# RobotBoard4.net
KiCad netlist of a schematic drawn in EAGLE
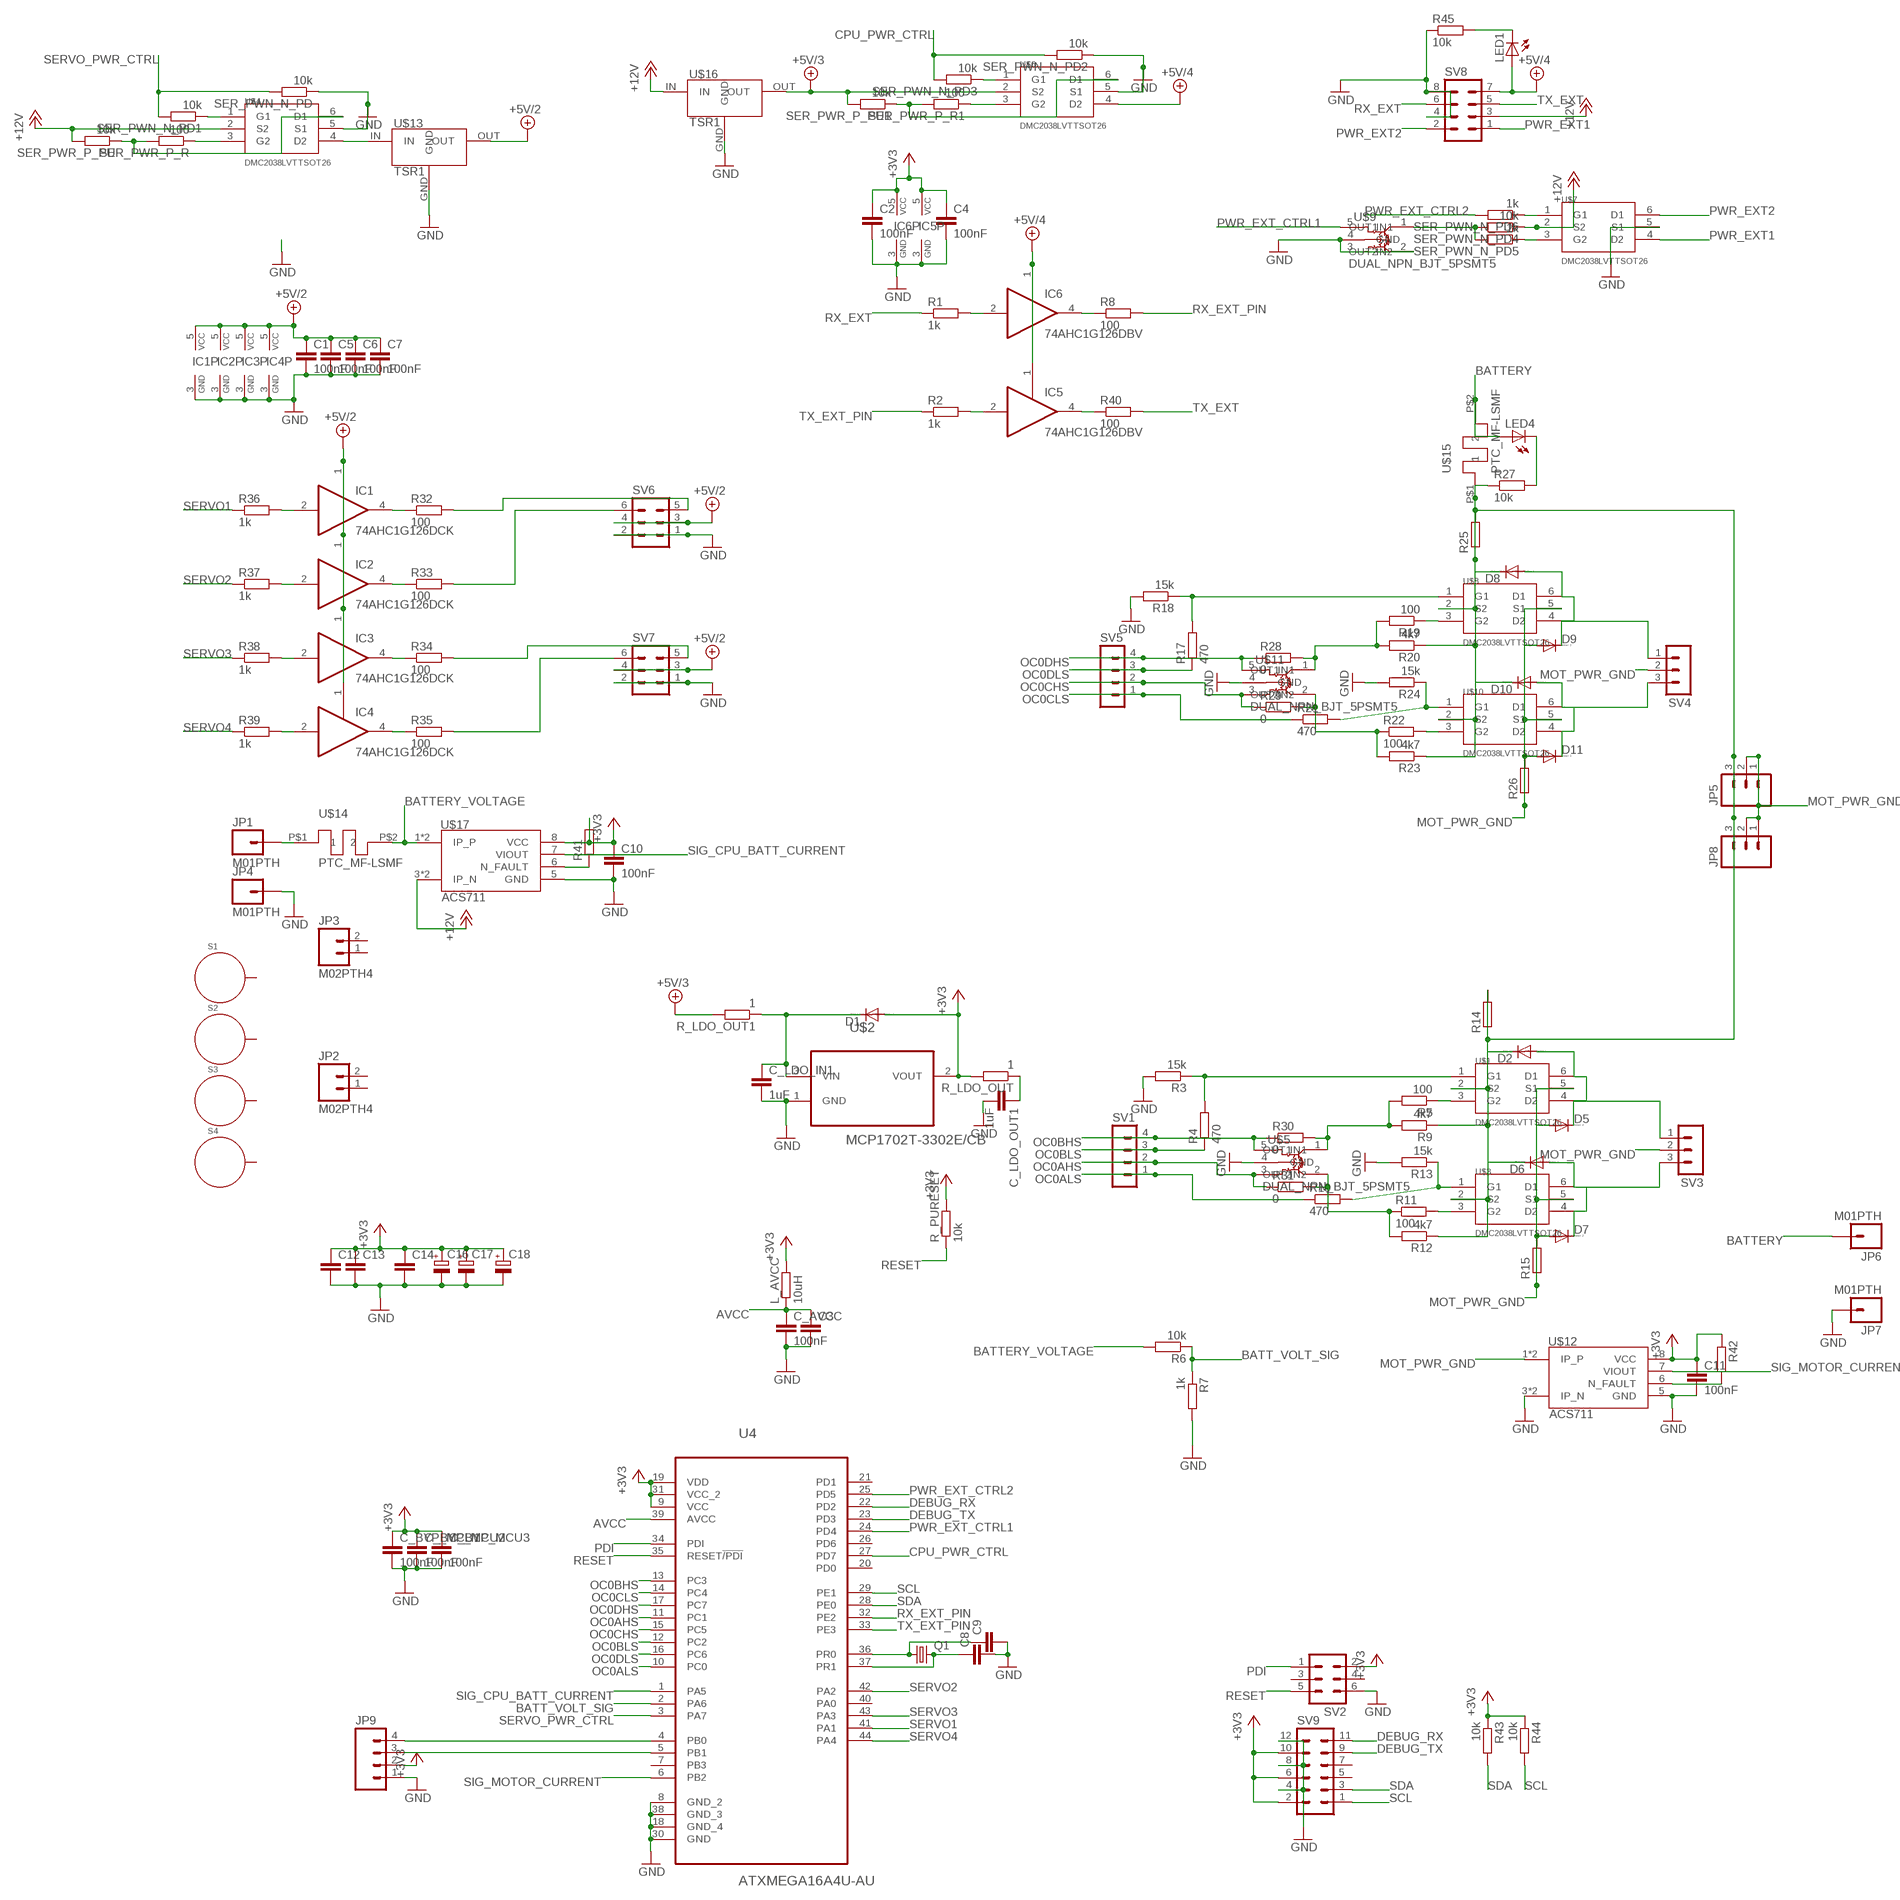
[diagram p0: schematic, sheet 1]

(export (version "E")
  (design (tool "Eeschema 10.0.6"))
  (components
    (comp (ref "C1")
      (value "100nF")
      (footprint "eagle-import:C0603")
      (libsource (lib "eagle-import") (part "C-EUC0603"))
    )
    (comp (ref "C2")
      (value "100nF")
      (footprint "eagle-import:C0603K")
      (libsource (lib "eagle-import") (part "C-EUC0603K"))
    )
    (comp (ref "C3")
      (value "C-EUC1206K")
      (footprint "eagle-import:C1206K")
      (libsource (lib "eagle-import") (part "C-EUC1206K"))
    )
    (comp (ref "C4")
      (value "100nF")
      (footprint "eagle-import:C0603K")
      (libsource (lib "eagle-import") (part "C-EUC0603K"))
    )
    (comp (ref "C5")
      (value "100nF")
      (footprint "eagle-import:C0603")
      (libsource (lib "eagle-import") (part "C-EUC0603"))
    )
    (comp (ref "C6")
      (value "100nF")
      (footprint "eagle-import:C0603")
      (libsource (lib "eagle-import") (part "C-EUC0603"))
    )
    (comp (ref "C7")
      (value "100nF")
      (footprint "eagle-import:C0603")
      (libsource (lib "eagle-import") (part "C-EUC0603"))
    )
    (comp (ref "C8")
      (value "C-EUC0603K")
      (footprint "eagle-import:C0603K")
      (libsource (lib "eagle-import") (part "C-EUC0603K"))
    )
    (comp (ref "C9")
      (value "C-EUC0603K")
      (footprint "eagle-import:C0603K")
      (libsource (lib "eagle-import") (part "C-EUC0603K"))
    )
    (comp (ref "C10")
      (value "100nF")
      (footprint "eagle-import:C0603K")
      (libsource (lib "eagle-import") (part "C-EUC0603K"))
    )
    (comp (ref "C11")
      (value "100nF")
      (footprint "eagle-import:C0603K")
      (libsource (lib "eagle-import") (part "C-EUC0603K"))
    )
    (comp (ref "C12")
      (value "C-EUC0805K")
      (footprint "eagle-import:C0805K")
      (libsource (lib "eagle-import") (part "C-EUC0805K"))
    )
    (comp (ref "C13")
      (value "C-EUC0805K")
      (footprint "eagle-import:C0805K")
      (libsource (lib "eagle-import") (part "C-EUC0805K"))
    )
    (comp (ref "C14")
      (value "C-EUC1210")
      (footprint "eagle-import:C1210")
      (libsource (lib "eagle-import") (part "C-EUC1210"))
    )
    (comp (ref "C16")
      (value "CPOL-EUE2.5-6")
      (footprint "eagle-import:E2,5-6")
      (libsource (lib "eagle-import") (part "CPOL-EUE2.5-6"))
    )
    (comp (ref "C17")
      (value "CPOL-EUE2.5-6")
      (footprint "eagle-import:E2,5-6")
      (libsource (lib "eagle-import") (part "CPOL-EUE2.5-6"))
    )
    (comp (ref "C18")
      (value "CPOL-EU153CLV-0505")
      (footprint "eagle-import:153CLV-0505")
      (libsource (lib "eagle-import") (part "CPOL-EU153CLV-0505"))
    )
    (comp (ref "C_AVCC")
      (value "100nF")
      (footprint "eagle-import:C0603")
      (libsource (lib "eagle-import") (part "C-EUC0603"))
    )
    (comp (ref "C_BYP_MCU1")
      (value "100nF")
      (footprint "eagle-import:C0603")
      (libsource (lib "eagle-import") (part "C-EUC0603"))
    )
    (comp (ref "C_BYP_MCU2")
      (value "100nF")
      (footprint "eagle-import:C0603")
      (libsource (lib "eagle-import") (part "C-EUC0603"))
    )
    (comp (ref "C_BYP_MCU3")
      (value "100nF")
      (footprint "eagle-import:C0603")
      (libsource (lib "eagle-import") (part "C-EUC0603"))
    )
    (comp (ref "C_LDO_IN1")
      (value "1uF")
      (footprint "eagle-import:C0805")
      (libsource (lib "eagle-import") (part "C-EUC0805"))
    )
    (comp (ref "C_LDO_OUT1")
      (value "1uF")
      (footprint "eagle-import:C0805")
      (libsource (lib "eagle-import") (part "C-EUC0805"))
    )
    (comp (ref "D1")
      (value "DIODE-SOD523")
      (footprint "eagle-import:SOD523")
      (libsource (lib "eagle-import") (part "DIODE-SOD523"))
    )
    (comp (ref "D2")
      (value "DIODE-SOD123")
      (footprint "eagle-import:SOD123")
      (libsource (lib "eagle-import") (part "DIODE-SOD123"))
    )
    (comp (ref "D5")
      (value "DIODE-SOD123")
      (footprint "eagle-import:SOD123")
      (libsource (lib "eagle-import") (part "DIODE-SOD123"))
    )
    (comp (ref "D6")
      (value "DIODE-SOD123")
      (footprint "eagle-import:SOD123")
      (libsource (lib "eagle-import") (part "DIODE-SOD123"))
    )
    (comp (ref "D7")
      (value "DIODE-SOD123")
      (footprint "eagle-import:SOD123")
      (libsource (lib "eagle-import") (part "DIODE-SOD123"))
    )
    (comp (ref "D8")
      (value "DIODE-SOD123")
      (footprint "eagle-import:SOD123")
      (libsource (lib "eagle-import") (part "DIODE-SOD123"))
    )
    (comp (ref "D9")
      (value "DIODE-SOD123")
      (footprint "eagle-import:SOD123")
      (libsource (lib "eagle-import") (part "DIODE-SOD123"))
    )
    (comp (ref "D10")
      (value "DIODE-SOD123")
      (footprint "eagle-import:SOD123")
      (libsource (lib "eagle-import") (part "DIODE-SOD123"))
    )
    (comp (ref "D11")
      (value "DIODE-SOD123")
      (footprint "eagle-import:SOD123")
      (libsource (lib "eagle-import") (part "DIODE-SOD123"))
    )
    (comp (ref "IC1")
      (value "74AHC1G126DCK")
      (footprint "eagle-import:SC70-5")
      (libsource (lib "eagle-import") (part "741G126DCKAHC"))
    )
    (comp (ref "IC2")
      (value "74AHC1G126DCK")
      (footprint "eagle-import:SC70-5")
      (libsource (lib "eagle-import") (part "741G126DCKAHC"))
    )
    (comp (ref "IC3")
      (value "74AHC1G126DCK")
      (footprint "eagle-import:SC70-5")
      (libsource (lib "eagle-import") (part "741G126DCKAHC"))
    )
    (comp (ref "IC4")
      (value "74AHC1G126DCK")
      (footprint "eagle-import:SC70-5")
      (libsource (lib "eagle-import") (part "741G126DCKAHC"))
    )
    (comp (ref "IC5")
      (value "74AHC1G126DBV")
      (footprint "eagle-import:SOT23-5")
      (libsource (lib "eagle-import") (part "741G126DBVAHC"))
    )
    (comp (ref "IC6")
      (value "74AHC1G126DBV")
      (footprint "eagle-import:SOT23-5")
      (libsource (lib "eagle-import") (part "741G126DBVAHC"))
    )
    (comp (ref "JP1")
      (value "M01PTH")
      (footprint "eagle-import:1X01")
      (libsource (lib "eagle-import") (part "M01PTH"))
    )
    (comp (ref "JP2")
      (value "M02PTH4")
      (footprint "eagle-import:1X02_XTRA_BIG")
      (libsource (lib "eagle-import") (part "M02PTH4"))
    )
    (comp (ref "JP3")
      (value "M02PTH4")
      (footprint "eagle-import:1X02_XTRA_BIG")
      (libsource (lib "eagle-import") (part "M02PTH4"))
    )
    (comp (ref "JP4")
      (value "M01PTH")
      (footprint "eagle-import:1X01")
      (libsource (lib "eagle-import") (part "M01PTH"))
    )
    (comp (ref "JP5")
      (value "M03PTH")
      (footprint "eagle-import:1X03")
      (libsource (lib "eagle-import") (part "M03PTH"))
    )
    (comp (ref "JP6")
      (value "M01PTH")
      (footprint "eagle-import:1X01")
      (libsource (lib "eagle-import") (part "M01PTH"))
    )
    (comp (ref "JP7")
      (value "M01PTH")
      (footprint "eagle-import:1X01")
      (libsource (lib "eagle-import") (part "M01PTH"))
    )
    (comp (ref "JP8")
      (value "M03PTH")
      (footprint "eagle-import:1X03")
      (libsource (lib "eagle-import") (part "M03PTH"))
    )
    (comp (ref "JP9")
      (value "M04PTH")
      (footprint "eagle-import:1X04")
      (libsource (lib "eagle-import") (part "M04PTH"))
    )
    (comp (ref "LED1")
      (value "LEDSML0603")
      (footprint "eagle-import:SML0603")
      (libsource (lib "eagle-import") (part "LEDSML0603"))
    )
    (comp (ref "LED4")
      (value "LEDSML0603")
      (footprint "eagle-import:SML0603")
      (libsource (lib "eagle-import") (part "LEDSML0603"))
    )
    (comp (ref "L_AVCC")
      (value "10uH")
      (footprint "eagle-import:R0805")
      (libsource (lib "eagle-import") (part "R-EU_R0805"))
    )
    (comp (ref "Q1")
      (value "CRYSTALHC49S")
      (footprint "eagle-import:HC49_S")
      (libsource (lib "eagle-import") (part "CRYSTALHC49S"))
    )
    (comp (ref "R1")
      (value "1k")
      (footprint "eagle-import:R0603")
      (libsource (lib "eagle-import") (part "R-EU_R0603"))
    )
    (comp (ref "R2")
      (value "1k")
      (footprint "eagle-import:R0603")
      (libsource (lib "eagle-import") (part "R-EU_R0603"))
    )
    (comp (ref "R3")
      (value "15k")
      (footprint "eagle-import:R0603")
      (libsource (lib "eagle-import") (part "R-EU_R0603"))
    )
    (comp (ref "R4")
      (value "470")
      (footprint "eagle-import:R0603")
      (libsource (lib "eagle-import") (part "R-EU_R0603"))
    )
    (comp (ref "R5")
      (value "100")
      (footprint "eagle-import:R0603")
      (libsource (lib "eagle-import") (part "R-EU_R0603"))
    )
    (comp (ref "R6")
      (value "10k")
      (footprint "eagle-import:R0603")
      (libsource (lib "eagle-import") (part "R-EU_R0603"))
    )
    (comp (ref "R7")
      (value "1k")
      (footprint "eagle-import:R0603")
      (libsource (lib "eagle-import") (part "R-EU_R0603"))
    )
    (comp (ref "R8")
      (value "100")
      (footprint "eagle-import:R0603")
      (libsource (lib "eagle-import") (part "R-EU_R0603"))
    )
    (comp (ref "R9")
      (value "4k7")
      (footprint "eagle-import:R0603")
      (libsource (lib "eagle-import") (part "R-EU_R0603"))
    )
    (comp (ref "R10")
      (value "470")
      (footprint "eagle-import:R0603")
      (libsource (lib "eagle-import") (part "R-EU_R0603"))
    )
    (comp (ref "R11")
      (value "100")
      (footprint "eagle-import:R0603")
      (libsource (lib "eagle-import") (part "R-EU_R0603"))
    )
    (comp (ref "R12")
      (value "4k7")
      (footprint "eagle-import:R0603")
      (libsource (lib "eagle-import") (part "R-EU_R0603"))
    )
    (comp (ref "R13")
      (value "15k")
      (footprint "eagle-import:R0603")
      (libsource (lib "eagle-import") (part "R-EU_R0603"))
    )
    (comp (ref "R14")
      (value "R-EU_0204/5")
      (footprint "eagle-import:0204_5")
      (libsource (lib "eagle-import") (part "R-EU_0204/5"))
    )
    (comp (ref "R15")
      (value "R-EU_0204/5")
      (footprint "eagle-import:0204_5")
      (libsource (lib "eagle-import") (part "R-EU_0204/5"))
    )
    (comp (ref "R17")
      (value "470")
      (footprint "eagle-import:R0603")
      (libsource (lib "eagle-import") (part "R-EU_R0603"))
    )
    (comp (ref "R18")
      (value "15k")
      (footprint "eagle-import:R0603")
      (libsource (lib "eagle-import") (part "R-EU_R0603"))
    )
    (comp (ref "R19")
      (value "100")
      (footprint "eagle-import:R0603")
      (libsource (lib "eagle-import") (part "R-EU_R0603"))
    )
    (comp (ref "R20")
      (value "4k7")
      (footprint "eagle-import:R0603")
      (libsource (lib "eagle-import") (part "R-EU_R0603"))
    )
    (comp (ref "R21")
      (value "470")
      (footprint "eagle-import:R0603")
      (libsource (lib "eagle-import") (part "R-EU_R0603"))
    )
    (comp (ref "R22")
      (value "100")
      (footprint "eagle-import:R0603")
      (libsource (lib "eagle-import") (part "R-EU_R0603"))
    )
    (comp (ref "R23")
      (value "4k7")
      (footprint "eagle-import:R0603")
      (libsource (lib "eagle-import") (part "R-EU_R0603"))
    )
    (comp (ref "R24")
      (value "15k")
      (footprint "eagle-import:R0603")
      (libsource (lib "eagle-import") (part "R-EU_R0603"))
    )
    (comp (ref "R25")
      (value "R-EU_0204/5")
      (footprint "eagle-import:0204_5")
      (libsource (lib "eagle-import") (part "R-EU_0204/5"))
    )
    (comp (ref "R26")
      (value "R-EU_0204/5")
      (footprint "eagle-import:0204_5")
      (libsource (lib "eagle-import") (part "R-EU_0204/5"))
    )
    (comp (ref "R27")
      (value "10k")
      (footprint "eagle-import:R0603")
      (libsource (lib "eagle-import") (part "R-EU_R0603"))
    )
    (comp (ref "R28")
      (value "0")
      (footprint "eagle-import:R0603")
      (libsource (lib "eagle-import") (part "R-EU_R0603"))
    )
    (comp (ref "R29")
      (value "0")
      (footprint "eagle-import:R0603")
      (libsource (lib "eagle-import") (part "R-EU_R0603"))
    )
    (comp (ref "R30")
      (value "0")
      (footprint "eagle-import:R0603")
      (libsource (lib "eagle-import") (part "R-EU_R0603"))
    )
    (comp (ref "R31")
      (value "0")
      (footprint "eagle-import:R0603")
      (libsource (lib "eagle-import") (part "R-EU_R0603"))
    )
    (comp (ref "R32")
      (value "100")
      (footprint "eagle-import:R0603")
      (libsource (lib "eagle-import") (part "R-EU_R0603"))
    )
    (comp (ref "R33")
      (value "100")
      (footprint "eagle-import:R0603")
      (libsource (lib "eagle-import") (part "R-EU_R0603"))
    )
    (comp (ref "R34")
      (value "100")
      (footprint "eagle-import:R0603")
      (libsource (lib "eagle-import") (part "R-EU_R0603"))
    )
    (comp (ref "R35")
      (value "100")
      (footprint "eagle-import:R0603")
      (libsource (lib "eagle-import") (part "R-EU_R0603"))
    )
    (comp (ref "R36")
      (value "1k")
      (footprint "eagle-import:R0603")
      (libsource (lib "eagle-import") (part "R-EU_R0603"))
    )
    (comp (ref "R37")
      (value "1k")
      (footprint "eagle-import:R0603")
      (libsource (lib "eagle-import") (part "R-EU_R0603"))
    )
    (comp (ref "R38")
      (value "1k")
      (footprint "eagle-import:R0603")
      (libsource (lib "eagle-import") (part "R-EU_R0603"))
    )
    (comp (ref "R39")
      (value "1k")
      (footprint "eagle-import:R0603")
      (libsource (lib "eagle-import") (part "R-EU_R0603"))
    )
    (comp (ref "R40")
      (value "100")
      (footprint "eagle-import:R0603")
      (libsource (lib "eagle-import") (part "R-EU_R0603"))
    )
    (comp (ref "R41")
      (value "R-EU_R0603")
      (footprint "eagle-import:R0603")
      (libsource (lib "eagle-import") (part "R-EU_R0603"))
    )
    (comp (ref "R42")
      (value "R-EU_R0603")
      (footprint "eagle-import:R0603")
      (libsource (lib "eagle-import") (part "R-EU_R0603"))
    )
    (comp (ref "R43")
      (value "10k")
      (footprint "eagle-import:R0603")
      (libsource (lib "eagle-import") (part "R-EU_R0603"))
    )
    (comp (ref "R44")
      (value "10k")
      (footprint "eagle-import:R0603")
      (libsource (lib "eagle-import") (part "R-EU_R0603"))
    )
    (comp (ref "R45")
      (value "10k")
      (footprint "eagle-import:R0603")
      (libsource (lib "eagle-import") (part "R-EU_R0603"))
    )
    (comp (ref "R_LDO_OUT")
      (value "1")
      (footprint "eagle-import:R0603")
      (libsource (lib "eagle-import") (part "R-EU_R0603"))
    )
    (comp (ref "R_LDO_OUT1")
      (value "1")
      (footprint "eagle-import:R0603")
      (libsource (lib "eagle-import") (part "R-EU_R0603"))
    )
    (comp (ref "R_PURESET")
      (value "10k")
      (footprint "eagle-import:R0603")
      (libsource (lib "eagle-import") (part "R-EU_R0603"))
    )
    (comp (ref "S1")
      (value "STANDOFF_ELECTRICAL")
      (footprint "eagle-import:STANDOFF-ELECTRICAL")
      (libsource (lib "eagle-import") (part "STANDOFF_ELECTRICAL"))
    )
    (comp (ref "S2")
      (value "STANDOFF_ELECTRICAL")
      (footprint "eagle-import:STANDOFF-ELECTRICAL")
      (libsource (lib "eagle-import") (part "STANDOFF_ELECTRICAL"))
    )
    (comp (ref "S3")
      (value "STANDOFF_ELECTRICAL")
      (footprint "eagle-import:STANDOFF-ELECTRICAL")
      (libsource (lib "eagle-import") (part "STANDOFF_ELECTRICAL"))
    )
    (comp (ref "S4")
      (value "STANDOFF_ELECTRICAL")
      (footprint "eagle-import:STANDOFF-ELECTRICAL")
      (libsource (lib "eagle-import") (part "STANDOFF_ELECTRICAL"))
    )
    (comp (ref "SER_PWN_N_PD")
      (value "10k")
      (footprint "eagle-import:R0603")
      (libsource (lib "eagle-import") (part "R-EU_R0603"))
    )
    (comp (ref "SER_PWN_N_PD1")
      (value "10k")
      (footprint "eagle-import:R0603")
      (libsource (lib "eagle-import") (part "R-EU_R0603"))
    )
    (comp (ref "SER_PWN_N_PD2")
      (value "10k")
      (footprint "eagle-import:R0603")
      (libsource (lib "eagle-import") (part "R-EU_R0603"))
    )
    (comp (ref "SER_PWN_N_PD3")
      (value "10k")
      (footprint "eagle-import:R0603")
      (libsource (lib "eagle-import") (part "R-EU_R0603"))
    )
    (comp (ref "SER_PWN_N_PD4")
      (value "10k")
      (footprint "eagle-import:R0603")
      (libsource (lib "eagle-import") (part "R-EU_R0603"))
    )
    (comp (ref "SER_PWN_N_PD5")
      (value "1k")
      (footprint "eagle-import:R0603")
      (libsource (lib "eagle-import") (part "R-EU_R0603"))
    )
    (comp (ref "SER_PWN_N_PD6")
      (value "1k")
      (footprint "eagle-import:R0603")
      (libsource (lib "eagle-import") (part "R-EU_R0603"))
    )
    (comp (ref "SER_PWR_P_PU")
      (value "10k")
      (footprint "eagle-import:R0603")
      (libsource (lib "eagle-import") (part "R-EU_R0603"))
    )
    (comp (ref "SER_PWR_P_PU1")
      (value "10k")
      (footprint "eagle-import:R0603")
      (libsource (lib "eagle-import") (part "R-EU_R0603"))
    )
    (comp (ref "SER_PWR_P_R")
      (value "100")
      (footprint "eagle-import:R0603")
      (libsource (lib "eagle-import") (part "R-EU_R0603"))
    )
    (comp (ref "SER_PWR_P_R1")
      (value "100")
      (footprint "eagle-import:R0603")
      (libsource (lib "eagle-import") (part "R-EU_R0603"))
    )
    (comp (ref "SV1")
      (value "MA04-1")
      (footprint "eagle-import:MA04-1")
      (libsource (lib "eagle-import") (part "MA04-1"))
    )
    (comp (ref "SV2")
      (value "MA03-2")
      (footprint "eagle-import:MA03-2")
      (libsource (lib "eagle-import") (part "MA03-2"))
    )
    (comp (ref "SV3")
      (value "MA03-1")
      (footprint "eagle-import:MA03-1")
      (libsource (lib "eagle-import") (part "MA03-1"))
    )
    (comp (ref "SV4")
      (value "MA03-1")
      (footprint "eagle-import:MA03-1")
      (libsource (lib "eagle-import") (part "MA03-1"))
    )
    (comp (ref "SV5")
      (value "MA04-1")
      (footprint "eagle-import:MA04-1")
      (libsource (lib "eagle-import") (part "MA04-1"))
    )
    (comp (ref "SV6")
      (value "MA03-2")
      (footprint "eagle-import:MA03-2")
      (libsource (lib "eagle-import") (part "MA03-2"))
    )
    (comp (ref "SV7")
      (value "MA03-2")
      (footprint "eagle-import:MA03-2")
      (libsource (lib "eagle-import") (part "MA03-2"))
    )
    (comp (ref "SV8")
      (value "MA04-2")
      (footprint "eagle-import:MA04-2")
      (libsource (lib "eagle-import") (part "MA04-2"))
    )
    (comp (ref "SV9")
      (value "MA06-2")
      (footprint "eagle-import:MA06-2")
      (libsource (lib "eagle-import") (part "MA06-2"))
    )
    (comp (ref "U$1")
      (value "DMC2038LVTTSOT26")
      (footprint "eagle-import:TSOT26")
      (libsource (lib "eagle-import") (part "DMC2038LVTTSOT26"))
    )
    (comp (ref "U$2")
      (value "MCP1702T-3302E/CB")
      (footprint "eagle-import:SOT95P255X145-3N")
      (libsource (lib "eagle-import") (part "MCP1702T-3302E/CB"))
    )
    (comp (ref "U$3")
      (value "DMC2038LVTTSOT26")
      (footprint "eagle-import:TSOT26")
      (libsource (lib "eagle-import") (part "DMC2038LVTTSOT26"))
    )
    (comp (ref "U$4")
      (value "DMC2038LVTTSOT26")
      (footprint "eagle-import:TSOT26")
      (libsource (lib "eagle-import") (part "DMC2038LVTTSOT26"))
    )
    (comp (ref "U$5")
      (value "DUAL_NPN_BJT_5PSMT5")
      (footprint "eagle-import:SC-74A")
      (libsource (lib "eagle-import") (part "DUAL_NPN_BJT_5PSMT5"))
    )
    (comp (ref "U$6")
      (value "DMC2038LVTTSOT26")
      (footprint "eagle-import:TSOT26")
      (libsource (lib "eagle-import") (part "DMC2038LVTTSOT26"))
    )
    (comp (ref "U$7")
      (value "DMC2038LVTTSOT26")
      (footprint "eagle-import:TSOT26")
      (libsource (lib "eagle-import") (part "DMC2038LVTTSOT26"))
    )
    (comp (ref "U$8")
      (value "DMC2038LVTTSOT26")
      (footprint "eagle-import:TSOT26")
      (libsource (lib "eagle-import") (part "DMC2038LVTTSOT26"))
    )
    (comp (ref "U$9")
      (value "DUAL_NPN_BJT_5PSMT5")
      (footprint "eagle-import:SC-74A")
      (libsource (lib "eagle-import") (part "DUAL_NPN_BJT_5PSMT5"))
    )
    (comp (ref "U$10")
      (value "DMC2038LVTTSOT26")
      (footprint "eagle-import:TSOT26")
      (libsource (lib "eagle-import") (part "DMC2038LVTTSOT26"))
    )
    (comp (ref "U$11")
      (value "DUAL_NPN_BJT_5PSMT5")
      (footprint "eagle-import:SC-74A")
      (libsource (lib "eagle-import") (part "DUAL_NPN_BJT_5PSMT5"))
    )
    (comp (ref "U$12")
      (value "ACS711")
      (footprint "eagle-import:SO08")
      (libsource (lib "eagle-import") (part "ACS711"))
    )
    (comp (ref "U$13")
      (value "TSR1")
      (footprint "eagle-import:TSR-1")
      (libsource (lib "eagle-import") (part "TSR1"))
    )
    (comp (ref "U$14")
      (value "PTC_MF-LSMF")
      (footprint "eagle-import:PTC_FUSE_BOURNS")
      (libsource (lib "eagle-import") (part "PTC_MF-LSMF"))
    )
    (comp (ref "U$15")
      (value "PTC_MF-LSMF")
      (footprint "eagle-import:PTC_FUSE_BOURNS")
      (libsource (lib "eagle-import") (part "PTC_MF-LSMF"))
    )
    (comp (ref "U$16")
      (value "TSR1")
      (footprint "eagle-import:TSR-1")
      (libsource (lib "eagle-import") (part "TSR1"))
    )
    (comp (ref "U$17")
      (value "ACS711")
      (footprint "eagle-import:SO08")
      (libsource (lib "eagle-import") (part "ACS711"))
    )
    (comp (ref "U4")
      (value "ATXMEGA16A4U-AU")
      (footprint "eagle-import:QFP80P1200X1200X120-44N")
      (libsource (lib "eagle-import") (part "ATXMEGA16A4U-AU"))
    )
  )
  (nets
    (net (code "1") (name "+3V3") (class "Default")
      (node (ref "C10") (pin "1") (pinfunction "1_1") (pintype "passive"))
      (node (ref "C11") (pin "1") (pinfunction "1_1") (pintype "passive"))
      (node (ref "C12") (pin "1") (pinfunction "1_1") (pintype "passive"))
      (node (ref "C13") (pin "1") (pinfunction "1_1") (pintype "passive"))
      (node (ref "C14") (pin "1") (pinfunction "1_1") (pintype "passive"))
      (node (ref "C16") (pin "+") (pinfunction "+_+") (pintype "passive"))
      (node (ref "C17") (pin "+") (pinfunction "+_+") (pintype "passive"))
      (node (ref "C18") (pin "+") (pinfunction "+_+") (pintype "passive"))
      (node (ref "C2") (pin "1") (pinfunction "1_1") (pintype "passive"))
      (node (ref "C4") (pin "1") (pinfunction "1_1") (pintype "passive"))
      (node (ref "C_BYP_MCU1") (pin "1") (pinfunction "1_1") (pintype "passive"))
      (node (ref "C_BYP_MCU2") (pin "1") (pinfunction "1_1") (pintype "passive"))
      (node (ref "C_BYP_MCU3") (pin "1") (pinfunction "1_1") (pintype "passive"))
      (node (ref "D1") (pin "A") (pinfunction "A_A") (pintype "passive"))
      (node (ref "IC5") (pin "5") (pinfunction "VCC_5") (pintype "power_in"))
      (node (ref "IC6") (pin "5") (pinfunction "VCC_5") (pintype "power_in"))
      (node (ref "JP9") (pin "2") (pinfunction "2_2") (pintype "passive"))
      (node (ref "L_AVCC") (pin "2") (pinfunction "2_2") (pintype "passive"))
      (node (ref "R41") (pin "2") (pinfunction "2_2") (pintype "passive"))
      (node (ref "R42") (pin "1") (pinfunction "1_1") (pintype "passive"))
      (node (ref "R43") (pin "1") (pinfunction "1_1") (pintype "passive"))
      (node (ref "R44") (pin "1") (pinfunction "1_1") (pintype "passive"))
      (node (ref "R_LDO_OUT") (pin "2") (pinfunction "2_2") (pintype "passive"))
      (node (ref "R_PURESET") (pin "2") (pinfunction "2_2") (pintype "passive"))
      (node (ref "SV2") (pin "2") (pinfunction "2_2") (pintype "passive"))
      (node (ref "SV9") (pin "10") (pinfunction "10_10") (pintype "passive"))
      (node (ref "SV9") (pin "2") (pinfunction "2_2") (pintype "passive"))
      (node (ref "SV9") (pin "6") (pinfunction "6_6") (pintype "passive"))
      (node (ref "U$12") (pin "8") (pinfunction "VCC_8") (pintype "bidirectional"))
      (node (ref "U$17") (pin "8") (pinfunction "VCC_8") (pintype "bidirectional"))
      (node (ref "U$2") (pin "2") (pinfunction "VOUT_2") (pintype "output"))
      (node (ref "U4") (pin "19") (pinfunction "VDD_19") (pintype "power_in"))
      (node (ref "U4") (pin "31") (pinfunction "VCC_2_31") (pintype "power_in"))
      (node (ref "U4") (pin "9") (pinfunction "VCC_9") (pintype "power_in"))
    )
    (net (code "2") (name "+5V{slash}2") (class "Default")
      (node (ref "C1") (pin "1") (pinfunction "1_1") (pintype "passive"))
      (node (ref "C5") (pin "1") (pinfunction "1_1") (pintype "passive"))
      (node (ref "C6") (pin "1") (pinfunction "1_1") (pintype "passive"))
      (node (ref "C7") (pin "1") (pinfunction "1_1") (pintype "passive"))
      (node (ref "IC1") (pin "1") (pinfunction "OE_1") (pintype "input"))
      (node (ref "IC1") (pin "5") (pinfunction "VCC_5") (pintype "power_in"))
      (node (ref "IC2") (pin "1") (pinfunction "OE_1") (pintype "input"))
      (node (ref "IC2") (pin "5") (pinfunction "VCC_5") (pintype "power_in"))
      (node (ref "IC3") (pin "1") (pinfunction "OE_1") (pintype "input"))
      (node (ref "IC3") (pin "5") (pinfunction "VCC_5") (pintype "power_in"))
      (node (ref "IC4") (pin "1") (pinfunction "OE_1") (pintype "input"))
      (node (ref "IC4") (pin "5") (pinfunction "VCC_5") (pintype "power_in"))
      (node (ref "SV6") (pin "3") (pinfunction "3_3") (pintype "passive"))
      (node (ref "SV6") (pin "4") (pinfunction "4_4") (pintype "passive"))
      (node (ref "SV7") (pin "3") (pinfunction "3_3") (pintype "passive"))
      (node (ref "SV7") (pin "4") (pinfunction "4_4") (pintype "passive"))
      (node (ref "U$13") (pin "OUT") (pinfunction "OUT_OUT") (pintype "bidirectional"))
    )
    (net (code "3") (name "+5V{slash}3") (class "Default")
      (node (ref "R_LDO_OUT1") (pin "2") (pinfunction "2_2") (pintype "passive"))
      (node (ref "SER_PWR_P_PU1") (pin "2") (pinfunction "2_2") (pintype "passive"))
      (node (ref "U$16") (pin "OUT") (pinfunction "OUT_OUT") (pintype "bidirectional"))
      (node (ref "U$6") (pin "2") (pinfunction "S2_2") (pintype "bidirectional"))
    )
    (net (code "4") (name "+5V{slash}4") (class "Default")
      (node (ref "IC5") (pin "1") (pinfunction "OE_1") (pintype "input"))
      (node (ref "IC6") (pin "1") (pinfunction "OE_1") (pintype "input"))
      (node (ref "LED1") (pin "A") (pinfunction "A_A") (pintype "passive"))
      (node (ref "SV8") (pin "7") (pinfunction "7_7") (pintype "passive"))
      (node (ref "U$6") (pin "4") (pinfunction "D2_4") (pintype "bidirectional"))
    )
    (net (code "5") (name "+12V") (class "Default")
      (node (ref "SER_PWN_N_PD4") (pin "1") (pinfunction "1_1") (pintype "passive"))
      (node (ref "SER_PWR_P_PU") (pin "2") (pinfunction "2_2") (pintype "passive"))
      (node (ref "SV8") (pin "3") (pinfunction "3_3") (pintype "passive"))
      (node (ref "U$16") (pin "IN") (pinfunction "IN_IN") (pintype "bidirectional"))
      (node (ref "U$17") (pin "3") (pinfunction "IP_N_3") (pintype "bidirectional"))
      (node (ref "U$17") (pin "4") (pinfunction "IP_N_4") (pintype "bidirectional"))
      (node (ref "U$4") (pin "2") (pinfunction "S2_2") (pintype "bidirectional"))
      (node (ref "U$7") (pin "2") (pinfunction "S2_2") (pintype "bidirectional"))
    )
    (net (code "6") (name "/AVCC") (class "Default")
      (node (ref "C3") (pin "1") (pinfunction "1_1") (pintype "passive"))
      (node (ref "C_AVCC") (pin "1") (pinfunction "1_1") (pintype "passive"))
      (node (ref "L_AVCC") (pin "1") (pinfunction "1_1") (pintype "passive"))
      (node (ref "U4") (pin "39") (pinfunction "AVCC_39") (pintype "power_in"))
    )
    (net (code "7") (name "/BATTERY") (class "Default")
      (node (ref "JP6") (pin "1") (pinfunction "1_1") (pintype "passive"))
      (node (ref "LED4") (pin "A") (pinfunction "A_A") (pintype "passive"))
      (node (ref "U$15") (pin "P$2") (pinfunction "2_P$2") (pintype "bidirectional"))
    )
    (net (code "8") (name "/BATTERY_VOLTAGE") (class "Default")
      (node (ref "R6") (pin "2") (pinfunction "2_2") (pintype "passive"))
      (node (ref "U$14") (pin "P$2") (pinfunction "2_P$2") (pintype "bidirectional"))
      (node (ref "U$17") (pin "1") (pinfunction "IP_P_1") (pintype "bidirectional"))
      (node (ref "U$17") (pin "2") (pinfunction "IP_P_2") (pintype "bidirectional"))
    )
    (net (code "9") (name "/BATT_VOLT_SIG") (class "Default")
      (node (ref "R6") (pin "1") (pinfunction "1_1") (pintype "passive"))
      (node (ref "R7") (pin "1") (pinfunction "1_1") (pintype "passive"))
      (node (ref "U4") (pin "2") (pinfunction "PA6_2") (pintype "bidirectional"))
    )
    (net (code "10") (name "/CPU_PWR_CTRL") (class "Default")
      (node (ref "SER_PWN_N_PD2") (pin "2") (pinfunction "2_2") (pintype "passive"))
      (node (ref "SER_PWN_N_PD3") (pin "2") (pinfunction "2_2") (pintype "passive"))
      (node (ref "U4") (pin "27") (pinfunction "PD7_27") (pintype "bidirectional"))
    )
    (net (code "11") (name "/DEBUG_RX") (class "Default")
      (node (ref "SV9") (pin "11") (pinfunction "11_11") (pintype "passive"))
      (node (ref "U4") (pin "22") (pinfunction "PD2_22") (pintype "bidirectional"))
    )
    (net (code "12") (name "/DEBUG_TX") (class "Default")
      (node (ref "SV9") (pin "9") (pinfunction "9_9") (pintype "passive"))
      (node (ref "U4") (pin "23") (pinfunction "PD3_23") (pintype "bidirectional"))
    )
    (net (code "13") (name "/MOT_PWR_GND") (class "Default")
      (node (ref "D11") (pin "A") (pinfunction "A_A") (pintype "passive"))
      (node (ref "D5") (pin "A") (pinfunction "A_A") (pintype "passive"))
      (node (ref "D7") (pin "A") (pinfunction "A_A") (pintype "passive"))
      (node (ref "D9") (pin "A") (pinfunction "A_A") (pintype "passive"))
      (node (ref "JP5") (pin "1") (pinfunction "1_1") (pintype "passive"))
      (node (ref "JP5") (pin "2") (pinfunction "2_2") (pintype "passive"))
      (node (ref "JP8") (pin "1") (pinfunction "1_1") (pintype "passive"))
      (node (ref "JP8") (pin "2") (pinfunction "2_2") (pintype "passive"))
      (node (ref "R15") (pin "1") (pinfunction "1_1") (pintype "passive"))
      (node (ref "R15") (pin "2") (pinfunction "2_2") (pintype "passive"))
      (node (ref "R26") (pin "1") (pinfunction "1_1") (pintype "passive"))
      (node (ref "R26") (pin "2") (pinfunction "2_2") (pintype "passive"))
      (node (ref "SV3") (pin "2") (pinfunction "2_2") (pintype "passive"))
      (node (ref "SV4") (pin "2") (pinfunction "2_2") (pintype "passive"))
      (node (ref "U$1") (pin "5") (pinfunction "S1_5") (pintype "bidirectional"))
      (node (ref "U$10") (pin "5") (pinfunction "S1_5") (pintype "bidirectional"))
      (node (ref "U$12") (pin "1") (pinfunction "IP_P_1") (pintype "bidirectional"))
      (node (ref "U$12") (pin "2") (pinfunction "IP_P_2") (pintype "bidirectional"))
      (node (ref "U$3") (pin "5") (pinfunction "S1_5") (pintype "bidirectional"))
      (node (ref "U$8") (pin "5") (pinfunction "S1_5") (pintype "bidirectional"))
    )
    (net (code "14") (name "/OC0AHS") (class "Default")
      (node (ref "R31") (pin "1") (pinfunction "1_1") (pintype "passive"))
      (node (ref "SV1") (pin "2") (pinfunction "2_2") (pintype "passive"))
      (node (ref "U$5") (pin "3") (pinfunction "IN2_3") (pintype "bidirectional"))
      (node (ref "U4") (pin "11") (pinfunction "PC1_11") (pintype "bidirectional"))
    )
    (net (code "15") (name "/OC0ALS") (class "Default")
      (node (ref "R10") (pin "1") (pinfunction "1_1") (pintype "passive"))
      (node (ref "SV1") (pin "1") (pinfunction "1_1") (pintype "passive"))
      (node (ref "U4") (pin "10") (pinfunction "PC0_10") (pintype "bidirectional"))
    )
    (net (code "16") (name "/OC0BHS") (class "Default")
      (node (ref "R30") (pin "1") (pinfunction "1_1") (pintype "passive"))
      (node (ref "SV1") (pin "4") (pinfunction "4_4") (pintype "passive"))
      (node (ref "U$5") (pin "5") (pinfunction "IN1_5") (pintype "bidirectional"))
      (node (ref "U4") (pin "13") (pinfunction "PC3_13") (pintype "bidirectional"))
    )
    (net (code "17") (name "/OC0BLS") (class "Default")
      (node (ref "R4") (pin "1") (pinfunction "1_1") (pintype "passive"))
      (node (ref "SV1") (pin "3") (pinfunction "3_3") (pintype "passive"))
      (node (ref "U4") (pin "12") (pinfunction "PC2_12") (pintype "bidirectional"))
    )
    (net (code "18") (name "/OC0CHS") (class "Default")
      (node (ref "R29") (pin "1") (pinfunction "1_1") (pintype "passive"))
      (node (ref "SV5") (pin "2") (pinfunction "2_2") (pintype "passive"))
      (node (ref "U$11") (pin "3") (pinfunction "IN2_3") (pintype "bidirectional"))
      (node (ref "U4") (pin "15") (pinfunction "PC5_15") (pintype "bidirectional"))
    )
    (net (code "19") (name "/OC0CLS") (class "Default")
      (node (ref "R21") (pin "1") (pinfunction "1_1") (pintype "passive"))
      (node (ref "SV5") (pin "1") (pinfunction "1_1") (pintype "passive"))
      (node (ref "U4") (pin "14") (pinfunction "PC4_14") (pintype "bidirectional"))
    )
    (net (code "20") (name "/OC0DHS") (class "Default")
      (node (ref "R28") (pin "1") (pinfunction "1_1") (pintype "passive"))
      (node (ref "SV5") (pin "4") (pinfunction "4_4") (pintype "passive"))
      (node (ref "U$11") (pin "5") (pinfunction "IN1_5") (pintype "bidirectional"))
      (node (ref "U4") (pin "17") (pinfunction "PC7_17") (pintype "bidirectional"))
    )
    (net (code "21") (name "/OC0DLS") (class "Default")
      (node (ref "R17") (pin "1") (pinfunction "1_1") (pintype "passive"))
      (node (ref "SV5") (pin "3") (pinfunction "3_3") (pintype "passive"))
      (node (ref "U4") (pin "16") (pinfunction "PC6_16") (pintype "bidirectional"))
    )
    (net (code "22") (name "/PDI") (class "Default")
      (node (ref "SV2") (pin "1") (pinfunction "1_1") (pintype "passive"))
      (node (ref "U4") (pin "34") (pinfunction "PDI_34") (pintype "passive"))
    )
    (net (code "23") (name "/PWR_EXT1") (class "Default")
      (node (ref "SV8") (pin "1") (pinfunction "1_1") (pintype "passive"))
      (node (ref "U$7") (pin "4") (pinfunction "D2_4") (pintype "bidirectional"))
    )
    (net (code "24") (name "/PWR_EXT2") (class "Default")
      (node (ref "SV8") (pin "2") (pinfunction "2_2") (pintype "passive"))
      (node (ref "U$7") (pin "6") (pinfunction "D1_6") (pintype "bidirectional"))
    )
    (net (code "25") (name "/PWR_EXT_CTRL1") (class "Default")
      (node (ref "U$9") (pin "5") (pinfunction "IN1_5") (pintype "bidirectional"))
      (node (ref "U4") (pin "24") (pinfunction "PD4_24") (pintype "bidirectional"))
    )
    (net (code "26") (name "/PWR_EXT_CTRL2") (class "Default")
      (node (ref "SER_PWN_N_PD6") (pin "2") (pinfunction "2_2") (pintype "passive"))
      (node (ref "U4") (pin "25") (pinfunction "PD5_25") (pintype "bidirectional"))
    )
    (net (code "27") (name "/RESET") (class "Default")
      (node (ref "R_PURESET") (pin "1") (pinfunction "1_1") (pintype "passive"))
      (node (ref "SV2") (pin "5") (pinfunction "5_5") (pintype "passive"))
      (node (ref "U4") (pin "35") (pinfunction "RESET~{/PDI}_35") (pintype "input"))
    )
    (net (code "28") (name "/RX_EXT") (class "Default")
      (node (ref "R1") (pin "1") (pinfunction "1_1") (pintype "passive"))
      (node (ref "SV8") (pin "6") (pinfunction "6_6") (pintype "passive"))
    )
    (net (code "29") (name "/RX_EXT_PIN") (class "Default")
      (node (ref "R8") (pin "2") (pinfunction "2_2") (pintype "passive"))
      (node (ref "U4") (pin "32") (pinfunction "PE2_32") (pintype "bidirectional"))
    )
    (net (code "30") (name "/SCL") (class "Default")
      (node (ref "R44") (pin "2") (pinfunction "2_2") (pintype "passive"))
      (node (ref "SV9") (pin "1") (pinfunction "1_1") (pintype "passive"))
      (node (ref "U4") (pin "29") (pinfunction "PE1_29") (pintype "bidirectional"))
    )
    (net (code "31") (name "/SDA") (class "Default")
      (node (ref "R43") (pin "2") (pinfunction "2_2") (pintype "passive"))
      (node (ref "SV9") (pin "3") (pinfunction "3_3") (pintype "passive"))
      (node (ref "U4") (pin "28") (pinfunction "PE0_28") (pintype "bidirectional"))
    )
    (net (code "32") (name "/SERVO1") (class "Default")
      (node (ref "R36") (pin "1") (pinfunction "1_1") (pintype "passive"))
      (node (ref "U4") (pin "41") (pinfunction "PA1_41") (pintype "bidirectional"))
    )
    (net (code "33") (name "/SERVO2") (class "Default")
      (node (ref "R37") (pin "1") (pinfunction "1_1") (pintype "passive"))
      (node (ref "U4") (pin "42") (pinfunction "PA2_42") (pintype "bidirectional"))
    )
    (net (code "34") (name "/SERVO3") (class "Default")
      (node (ref "R38") (pin "1") (pinfunction "1_1") (pintype "passive"))
      (node (ref "U4") (pin "43") (pinfunction "PA3_43") (pintype "bidirectional"))
    )
    (net (code "35") (name "/SERVO4") (class "Default")
      (node (ref "R39") (pin "1") (pinfunction "1_1") (pintype "passive"))
      (node (ref "U4") (pin "44") (pinfunction "PA4_44") (pintype "bidirectional"))
    )
    (net (code "36") (name "/SERVO_PWR_CTRL") (class "Default")
      (node (ref "SER_PWN_N_PD") (pin "2") (pinfunction "2_2") (pintype "passive"))
      (node (ref "SER_PWN_N_PD1") (pin "2") (pinfunction "2_2") (pintype "passive"))
      (node (ref "U4") (pin "3") (pinfunction "PA7_3") (pintype "bidirectional"))
    )
    (net (code "37") (name "/SIG_CPU_BATT_CURRENT") (class "Default")
      (node (ref "U$17") (pin "7") (pinfunction "VIOUT_7") (pintype "bidirectional"))
      (node (ref "U4") (pin "1") (pinfunction "PA5_1") (pintype "bidirectional"))
    )
    (net (code "38") (name "/SIG_MOTOR_CURRENT") (class "Default")
      (node (ref "U$12") (pin "7") (pinfunction "VIOUT_7") (pintype "bidirectional"))
      (node (ref "U4") (pin "6") (pinfunction "PB2_6") (pintype "bidirectional"))
    )
    (net (code "39") (name "/TX_EXT") (class "Default")
      (node (ref "R40") (pin "2") (pinfunction "2_2") (pintype "passive"))
      (node (ref "SV8") (pin "5") (pinfunction "5_5") (pintype "passive"))
    )
    (net (code "40") (name "/TX_EXT_PIN") (class "Default")
      (node (ref "R2") (pin "1") (pinfunction "1_1") (pintype "passive"))
      (node (ref "U4") (pin "33") (pinfunction "PE3_33") (pintype "bidirectional"))
    )
    (net (code "41") (name "GND") (class "Default")
      (node (ref "C1") (pin "2") (pinfunction "2_2") (pintype "passive"))
      (node (ref "C10") (pin "2") (pinfunction "2_2") (pintype "passive"))
      (node (ref "C11") (pin "2") (pinfunction "2_2") (pintype "passive"))
      (node (ref "C12") (pin "2") (pinfunction "2_2") (pintype "passive"))
      (node (ref "C13") (pin "2") (pinfunction "2_2") (pintype "passive"))
      (node (ref "C14") (pin "2") (pinfunction "2_2") (pintype "passive"))
      (node (ref "C16") (pin "-") (pinfunction "-_-") (pintype "passive"))
      (node (ref "C17") (pin "-") (pinfunction "-_-") (pintype "passive"))
      (node (ref "C18") (pin "-") (pinfunction "-_-") (pintype "passive"))
      (node (ref "C2") (pin "2") (pinfunction "2_2") (pintype "passive"))
      (node (ref "C3") (pin "2") (pinfunction "2_2") (pintype "passive"))
      (node (ref "C4") (pin "2") (pinfunction "2_2") (pintype "passive"))
      (node (ref "C5") (pin "2") (pinfunction "2_2") (pintype "passive"))
      (node (ref "C6") (pin "2") (pinfunction "2_2") (pintype "passive"))
      (node (ref "C7") (pin "2") (pinfunction "2_2") (pintype "passive"))
      (node (ref "C8") (pin "2") (pinfunction "2_2") (pintype "passive"))
      (node (ref "C9") (pin "2") (pinfunction "2_2") (pintype "passive"))
      (node (ref "C_AVCC") (pin "2") (pinfunction "2_2") (pintype "passive"))
      (node (ref "C_BYP_MCU1") (pin "2") (pinfunction "2_2") (pintype "passive"))
      (node (ref "C_BYP_MCU2") (pin "2") (pinfunction "2_2") (pintype "passive"))
      (node (ref "C_BYP_MCU3") (pin "2") (pinfunction "2_2") (pintype "passive"))
      (node (ref "C_LDO_IN1") (pin "2") (pinfunction "2_2") (pintype "passive"))
      (node (ref "C_LDO_OUT1") (pin "2") (pinfunction "2_2") (pintype "passive"))
      (node (ref "IC1") (pin "3") (pinfunction "GND_3") (pintype "power_in"))
      (node (ref "IC2") (pin "3") (pinfunction "GND_3") (pintype "power_in"))
      (node (ref "IC3") (pin "3") (pinfunction "GND_3") (pintype "power_in"))
      (node (ref "IC4") (pin "3") (pinfunction "GND_3") (pintype "power_in"))
      (node (ref "IC5") (pin "3") (pinfunction "GND_3") (pintype "power_in"))
      (node (ref "IC6") (pin "3") (pinfunction "GND_3") (pintype "power_in"))
      (node (ref "JP4") (pin "1") (pinfunction "1_1") (pintype "passive"))
      (node (ref "JP7") (pin "1") (pinfunction "1_1") (pintype "passive"))
      (node (ref "JP9") (pin "1") (pinfunction "1_1") (pintype "passive"))
      (node (ref "R13") (pin "2") (pinfunction "2_2") (pintype "passive"))
      (node (ref "R18") (pin "2") (pinfunction "2_2") (pintype "passive"))
      (node (ref "R24") (pin "2") (pinfunction "2_2") (pintype "passive"))
      (node (ref "R3") (pin "2") (pinfunction "2_2") (pintype "passive"))
      (node (ref "R45") (pin "1") (pinfunction "1_1") (pintype "passive"))
      (node (ref "R7") (pin "2") (pinfunction "2_2") (pintype "passive"))
      (node (ref "SER_PWN_N_PD") (pin "1") (pinfunction "1_1") (pintype "passive"))
      (node (ref "SER_PWN_N_PD2") (pin "1") (pinfunction "1_1") (pintype "passive"))
      (node (ref "SV2") (pin "6") (pinfunction "6_6") (pintype "passive"))
      (node (ref "SV6") (pin "1") (pinfunction "1_1") (pintype "passive"))
      (node (ref "SV6") (pin "2") (pinfunction "2_2") (pintype "passive"))
      (node (ref "SV7") (pin "1") (pinfunction "1_1") (pintype "passive"))
      (node (ref "SV7") (pin "2") (pinfunction "2_2") (pintype "passive"))
      (node (ref "SV8") (pin "4") (pinfunction "4_4") (pintype "passive"))
      (node (ref "SV8") (pin "8") (pinfunction "8_8") (pintype "passive"))
      (node (ref "SV9") (pin "12") (pinfunction "12_12") (pintype "passive"))
      (node (ref "SV9") (pin "4") (pinfunction "4_4") (pintype "passive"))
      (node (ref "SV9") (pin "8") (pinfunction "8_8") (pintype "passive"))
      (node (ref "U$11") (pin "4") (pinfunction "GND_4") (pintype "bidirectional"))
      (node (ref "U$12") (pin "3") (pinfunction "IP_N_3") (pintype "bidirectional"))
      (node (ref "U$12") (pin "4") (pinfunction "IP_N_4") (pintype "bidirectional"))
      (node (ref "U$12") (pin "5") (pinfunction "GND_5") (pintype "bidirectional"))
      (node (ref "U$13") (pin "GND") (pinfunction "GND_GND") (pintype "bidirectional"))
      (node (ref "U$16") (pin "GND") (pinfunction "GND_GND") (pintype "bidirectional"))
      (node (ref "U$17") (pin "5") (pinfunction "GND_5") (pintype "bidirectional"))
      (node (ref "U$2") (pin "1") (pinfunction "GND_1") (pintype "passive"))
      (node (ref "U$4") (pin "5") (pinfunction "S1_5") (pintype "bidirectional"))
      (node (ref "U$5") (pin "4") (pinfunction "GND_4") (pintype "bidirectional"))
      (node (ref "U$6") (pin "5") (pinfunction "S1_5") (pintype "bidirectional"))
      (node (ref "U$7") (pin "5") (pinfunction "S1_5") (pintype "bidirectional"))
      (node (ref "U$9") (pin "2") (pinfunction "OUT2_2") (pintype "bidirectional"))
      (node (ref "U$9") (pin "3") (pinfunction "IN2_3") (pintype "bidirectional"))
      (node (ref "U$9") (pin "4") (pinfunction "GND_4") (pintype "bidirectional"))
      (node (ref "U4") (pin "18") (pinfunction "GND_4_18") (pintype "passive"))
      (node (ref "U4") (pin "30") (pinfunction "GND_30") (pintype "passive"))
      (node (ref "U4") (pin "38") (pinfunction "GND_3_38") (pintype "passive"))
      (node (ref "U4") (pin "8") (pinfunction "GND_2_8") (pintype "passive"))
    )
    (net (code "42") (name "Net-(C_LDO_OUT1-Pad1)") (class "Default")
      (node (ref "C_LDO_OUT1") (pin "1") (pinfunction "1_1") (pintype "passive"))
      (node (ref "R_LDO_OUT") (pin "1") (pinfunction "1_1") (pintype "passive"))
    )
    (net (code "43") (name "Net-(IC1A-I)") (class "Default")
      (node (ref "IC1") (pin "2") (pinfunction "I_2") (pintype "input"))
      (node (ref "R36") (pin "2") (pinfunction "2_2") (pintype "passive"))
    )
    (net (code "44") (name "Net-(IC1A-O)") (class "Default")
      (node (ref "IC1") (pin "4") (pinfunction "O_4") (pintype "output"))
      (node (ref "R32") (pin "1") (pinfunction "1_1") (pintype "passive"))
    )
    (net (code "45") (name "Net-(IC2A-I)") (class "Default")
      (node (ref "IC2") (pin "2") (pinfunction "I_2") (pintype "input"))
      (node (ref "R37") (pin "2") (pinfunction "2_2") (pintype "passive"))
    )
    (net (code "46") (name "Net-(IC2A-O)") (class "Default")
      (node (ref "IC2") (pin "4") (pinfunction "O_4") (pintype "output"))
      (node (ref "R33") (pin "1") (pinfunction "1_1") (pintype "passive"))
    )
    (net (code "47") (name "Net-(IC3A-I)") (class "Default")
      (node (ref "IC3") (pin "2") (pinfunction "I_2") (pintype "input"))
      (node (ref "R38") (pin "2") (pinfunction "2_2") (pintype "passive"))
    )
    (net (code "48") (name "Net-(IC3A-O)") (class "Default")
      (node (ref "IC3") (pin "4") (pinfunction "O_4") (pintype "output"))
      (node (ref "R34") (pin "1") (pinfunction "1_1") (pintype "passive"))
    )
    (net (code "49") (name "Net-(IC4A-I)") (class "Default")
      (node (ref "IC4") (pin "2") (pinfunction "I_2") (pintype "input"))
      (node (ref "R39") (pin "2") (pinfunction "2_2") (pintype "passive"))
    )
    (net (code "50") (name "Net-(IC4A-O)") (class "Default")
      (node (ref "IC4") (pin "4") (pinfunction "O_4") (pintype "output"))
      (node (ref "R35") (pin "1") (pinfunction "1_1") (pintype "passive"))
    )
    (net (code "51") (name "Net-(IC5A-I)") (class "Default")
      (node (ref "IC5") (pin "2") (pinfunction "I_2") (pintype "input"))
      (node (ref "R2") (pin "2") (pinfunction "2_2") (pintype "passive"))
    )
    (net (code "52") (name "Net-(IC5A-O)") (class "Default")
      (node (ref "IC5") (pin "4") (pinfunction "O_4") (pintype "output"))
      (node (ref "R40") (pin "1") (pinfunction "1_1") (pintype "passive"))
    )
    (net (code "53") (name "Net-(IC6A-I)") (class "Default")
      (node (ref "IC6") (pin "2") (pinfunction "I_2") (pintype "input"))
      (node (ref "R1") (pin "2") (pinfunction "2_2") (pintype "passive"))
    )
    (net (code "54") (name "Net-(IC6A-O)") (class "Default")
      (node (ref "IC6") (pin "4") (pinfunction "O_4") (pintype "output"))
      (node (ref "R8") (pin "1") (pinfunction "1_1") (pintype "passive"))
    )
    (net (code "55") (name "Net-(LED1-PadC)") (class "Default")
      (node (ref "LED1") (pin "C") (pinfunction "C_C") (pintype "passive"))
      (node (ref "R45") (pin "2") (pinfunction "2_2") (pintype "passive"))
    )
    (net (code "56") (name "Net-(LED4-PadC)") (class "Default")
      (node (ref "LED4") (pin "C") (pinfunction "C_C") (pintype "passive"))
      (node (ref "R27") (pin "2") (pinfunction "2_2") (pintype "passive"))
    )
    (net (code "57") (name "Net-(R32-Pad2)") (class "Default")
      (node (ref "R32") (pin "2") (pinfunction "2_2") (pintype "passive"))
      (node (ref "SV6") (pin "5") (pinfunction "5_5") (pintype "passive"))
    )
    (net (code "58") (name "Net-(R33-Pad2)") (class "Default")
      (node (ref "R33") (pin "2") (pinfunction "2_2") (pintype "passive"))
      (node (ref "SV6") (pin "6") (pinfunction "6_6") (pintype "passive"))
    )
    (net (code "59") (name "Net-(R34-Pad2)") (class "Default")
      (node (ref "R34") (pin "2") (pinfunction "2_2") (pintype "passive"))
      (node (ref "SV7") (pin "5") (pinfunction "5_5") (pintype "passive"))
    )
    (net (code "60") (name "Net-(R35-Pad2)") (class "Default")
      (node (ref "R35") (pin "2") (pinfunction "2_2") (pintype "passive"))
      (node (ref "SV7") (pin "6") (pinfunction "6_6") (pintype "passive"))
    )
    (net (code "61") (name "Net-(U$1-D1)") (class "Default")
      (node (ref "D2") (pin "A") (pinfunction "A_A") (pintype "passive"))
      (node (ref "D5") (pin "C") (pinfunction "C_C") (pintype "passive"))
      (node (ref "SV3") (pin "1") (pinfunction "1_1") (pintype "passive"))
      (node (ref "U$1") (pin "4") (pinfunction "D2_4") (pintype "bidirectional"))
      (node (ref "U$1") (pin "6") (pinfunction "D1_6") (pintype "bidirectional"))
    )
    (net (code "62") (name "Net-(U$1-G1)") (class "Default")
      (node (ref "R3") (pin "1") (pinfunction "1_1") (pintype "passive"))
      (node (ref "R4") (pin "2") (pinfunction "2_2") (pintype "passive"))
      (node (ref "U$1") (pin "1") (pinfunction "G1_1") (pintype "bidirectional"))
    )
    (net (code "63") (name "Net-(U$1-G2)") (class "Default")
      (node (ref "R5") (pin "1") (pinfunction "1_1") (pintype "passive"))
      (node (ref "U$1") (pin "3") (pinfunction "G2_3") (pintype "bidirectional"))
    )
    (net (code "64") (name "Net-(U$1-S2)") (class "Default")
      (node (ref "D10") (pin "C") (pinfunction "C_C") (pintype "passive"))
      (node (ref "D2") (pin "C") (pinfunction "C_C") (pintype "passive"))
      (node (ref "D6") (pin "C") (pinfunction "C_C") (pintype "passive"))
      (node (ref "D8") (pin "C") (pinfunction "C_C") (pintype "passive"))
      (node (ref "JP5") (pin "3") (pinfunction "3_3") (pintype "passive"))
      (node (ref "JP8") (pin "3") (pinfunction "3_3") (pintype "passive"))
      (node (ref "R12") (pin "1") (pinfunction "1_1") (pintype "passive"))
      (node (ref "R14") (pin "1") (pinfunction "1_1") (pintype "passive"))
      (node (ref "R14") (pin "2") (pinfunction "2_2") (pintype "passive"))
      (node (ref "R20") (pin "1") (pinfunction "1_1") (pintype "passive"))
      (node (ref "R23") (pin "1") (pinfunction "1_1") (pintype "passive"))
      (node (ref "R25") (pin "1") (pinfunction "1_1") (pintype "passive"))
      (node (ref "R25") (pin "2") (pinfunction "2_2") (pintype "passive"))
      (node (ref "R27") (pin "1") (pinfunction "1_1") (pintype "passive"))
      (node (ref "R9") (pin "1") (pinfunction "1_1") (pintype "passive"))
      (node (ref "U$1") (pin "2") (pinfunction "S2_2") (pintype "bidirectional"))
      (node (ref "U$10") (pin "2") (pinfunction "S2_2") (pintype "bidirectional"))
      (node (ref "U$15") (pin "P$1") (pinfunction "1_P$1") (pintype "bidirectional"))
      (node (ref "U$3") (pin "2") (pinfunction "S2_2") (pintype "bidirectional"))
      (node (ref "U$8") (pin "2") (pinfunction "S2_2") (pintype "bidirectional"))
    )
    (net (code "65") (name "Net-(U$2-VIN)") (class "Default")
      (node (ref "C_LDO_IN1") (pin "1") (pinfunction "1_1") (pintype "passive"))
      (node (ref "D1") (pin "C") (pinfunction "C_C") (pintype "passive"))
      (node (ref "R_LDO_OUT1") (pin "1") (pinfunction "1_1") (pintype "passive"))
      (node (ref "U$2") (pin "3") (pinfunction "VIN_3") (pintype "input"))
    )
    (net (code "66") (name "Net-(U$3-D1)") (class "Default")
      (node (ref "D6") (pin "A") (pinfunction "A_A") (pintype "passive"))
      (node (ref "D7") (pin "C") (pinfunction "C_C") (pintype "passive"))
      (node (ref "SV3") (pin "3") (pinfunction "3_3") (pintype "passive"))
      (node (ref "U$3") (pin "4") (pinfunction "D2_4") (pintype "bidirectional"))
      (node (ref "U$3") (pin "6") (pinfunction "D1_6") (pintype "bidirectional"))
    )
    (net (code "67") (name "Net-(U$3-G1)") (class "Default")
      (node (ref "R10") (pin "2") (pinfunction "2_2") (pintype "passive"))
      (node (ref "R13") (pin "1") (pinfunction "1_1") (pintype "passive"))
      (node (ref "U$3") (pin "1") (pinfunction "G1_1") (pintype "bidirectional"))
    )
    (net (code "68") (name "Net-(U$3-G2)") (class "Default")
      (node (ref "R11") (pin "2") (pinfunction "2_2") (pintype "passive"))
      (node (ref "U$3") (pin "3") (pinfunction "G2_3") (pintype "bidirectional"))
    )
    (net (code "69") (name "Net-(U$4-D1)") (class "Default")
      (node (ref "SER_PWR_P_PU") (pin "1") (pinfunction "1_1") (pintype "passive"))
      (node (ref "SER_PWR_P_R") (pin "2") (pinfunction "2_2") (pintype "passive"))
      (node (ref "U$4") (pin "6") (pinfunction "D1_6") (pintype "bidirectional"))
    )
    (net (code "70") (name "Net-(U$4-D2)") (class "Default")
      (node (ref "U$13") (pin "IN") (pinfunction "IN_IN") (pintype "bidirectional"))
      (node (ref "U$4") (pin "4") (pinfunction "D2_4") (pintype "bidirectional"))
    )
    (net (code "71") (name "Net-(U$4-G1)") (class "Default")
      (node (ref "SER_PWN_N_PD1") (pin "1") (pinfunction "1_1") (pintype "passive"))
      (node (ref "U$4") (pin "1") (pinfunction "G1_1") (pintype "bidirectional"))
    )
    (net (code "72") (name "Net-(U$4-G2)") (class "Default")
      (node (ref "SER_PWR_P_R") (pin "1") (pinfunction "1_1") (pintype "passive"))
      (node (ref "U$4") (pin "3") (pinfunction "G2_3") (pintype "bidirectional"))
    )
    (net (code "73") (name "Net-(U$5-OUT1)") (class "Default")
      (node (ref "R30") (pin "2") (pinfunction "2_2") (pintype "passive"))
      (node (ref "R5") (pin "2") (pinfunction "2_2") (pintype "passive"))
      (node (ref "R9") (pin "2") (pinfunction "2_2") (pintype "passive"))
      (node (ref "U$5") (pin "1") (pinfunction "OUT1_1") (pintype "bidirectional"))
    )
    (net (code "74") (name "Net-(U$5-OUT2)") (class "Default")
      (node (ref "R11") (pin "1") (pinfunction "1_1") (pintype "passive"))
      (node (ref "R12") (pin "2") (pinfunction "2_2") (pintype "passive"))
      (node (ref "R31") (pin "2") (pinfunction "2_2") (pintype "passive"))
      (node (ref "U$5") (pin "2") (pinfunction "OUT2_2") (pintype "bidirectional"))
    )
    (net (code "75") (name "Net-(U$6-D1)") (class "Default")
      (node (ref "SER_PWR_P_PU1") (pin "1") (pinfunction "1_1") (pintype "passive"))
      (node (ref "SER_PWR_P_R1") (pin "2") (pinfunction "2_2") (pintype "passive"))
      (node (ref "U$6") (pin "6") (pinfunction "D1_6") (pintype "bidirectional"))
    )
    (net (code "76") (name "Net-(U$6-G1)") (class "Default")
      (node (ref "SER_PWN_N_PD3") (pin "1") (pinfunction "1_1") (pintype "passive"))
      (node (ref "U$6") (pin "1") (pinfunction "G1_1") (pintype "bidirectional"))
    )
    (net (code "77") (name "Net-(U$6-G2)") (class "Default")
      (node (ref "SER_PWR_P_R1") (pin "1") (pinfunction "1_1") (pintype "passive"))
      (node (ref "U$6") (pin "3") (pinfunction "G2_3") (pintype "bidirectional"))
    )
    (net (code "78") (name "Net-(U$7-G1)") (class "Default")
      (node (ref "SER_PWN_N_PD6") (pin "1") (pinfunction "1_1") (pintype "passive"))
      (node (ref "U$7") (pin "1") (pinfunction "G1_1") (pintype "bidirectional"))
    )
    (net (code "79") (name "Net-(U$7-G2)") (class "Default")
      (node (ref "SER_PWN_N_PD5") (pin "1") (pinfunction "1_1") (pintype "passive"))
      (node (ref "U$7") (pin "3") (pinfunction "G2_3") (pintype "bidirectional"))
    )
    (net (code "80") (name "Net-(U$8-D1)") (class "Default")
      (node (ref "D8") (pin "A") (pinfunction "A_A") (pintype "passive"))
      (node (ref "D9") (pin "C") (pinfunction "C_C") (pintype "passive"))
      (node (ref "SV4") (pin "1") (pinfunction "1_1") (pintype "passive"))
      (node (ref "U$8") (pin "4") (pinfunction "D2_4") (pintype "bidirectional"))
      (node (ref "U$8") (pin "6") (pinfunction "D1_6") (pintype "bidirectional"))
    )
    (net (code "81") (name "Net-(U$8-G1)") (class "Default")
      (node (ref "R17") (pin "2") (pinfunction "2_2") (pintype "passive"))
      (node (ref "R18") (pin "1") (pinfunction "1_1") (pintype "passive"))
      (node (ref "U$8") (pin "1") (pinfunction "G1_1") (pintype "bidirectional"))
    )
    (net (code "82") (name "Net-(U$8-G2)") (class "Default")
      (node (ref "R19") (pin "1") (pinfunction "1_1") (pintype "passive"))
      (node (ref "U$8") (pin "3") (pinfunction "G2_3") (pintype "bidirectional"))
    )
    (net (code "83") (name "Net-(U$9-OUT1)") (class "Default")
      (node (ref "SER_PWN_N_PD4") (pin "2") (pinfunction "2_2") (pintype "passive"))
      (node (ref "SER_PWN_N_PD5") (pin "2") (pinfunction "2_2") (pintype "passive"))
      (node (ref "U$9") (pin "1") (pinfunction "OUT1_1") (pintype "bidirectional"))
    )
    (net (code "84") (name "Net-(U$10-D1)") (class "Default")
      (node (ref "D10") (pin "A") (pinfunction "A_A") (pintype "passive"))
      (node (ref "D11") (pin "C") (pinfunction "C_C") (pintype "passive"))
      (node (ref "SV4") (pin "3") (pinfunction "3_3") (pintype "passive"))
      (node (ref "U$10") (pin "4") (pinfunction "D2_4") (pintype "bidirectional"))
      (node (ref "U$10") (pin "6") (pinfunction "D1_6") (pintype "bidirectional"))
    )
    (net (code "85") (name "Net-(U$10-G1)") (class "Default")
      (node (ref "R21") (pin "2") (pinfunction "2_2") (pintype "passive"))
      (node (ref "R24") (pin "1") (pinfunction "1_1") (pintype "passive"))
      (node (ref "U$10") (pin "1") (pinfunction "G1_1") (pintype "bidirectional"))
    )
    (net (code "86") (name "Net-(U$10-G2)") (class "Default")
      (node (ref "R22") (pin "2") (pinfunction "2_2") (pintype "passive"))
      (node (ref "U$10") (pin "3") (pinfunction "G2_3") (pintype "bidirectional"))
    )
    (net (code "87") (name "Net-(U$11-OUT1)") (class "Default")
      (node (ref "R19") (pin "2") (pinfunction "2_2") (pintype "passive"))
      (node (ref "R20") (pin "2") (pinfunction "2_2") (pintype "passive"))
      (node (ref "R28") (pin "2") (pinfunction "2_2") (pintype "passive"))
      (node (ref "U$11") (pin "1") (pinfunction "OUT1_1") (pintype "bidirectional"))
    )
    (net (code "88") (name "Net-(U$11-OUT2)") (class "Default")
      (node (ref "R22") (pin "1") (pinfunction "1_1") (pintype "passive"))
      (node (ref "R23") (pin "2") (pinfunction "2_2") (pintype "passive"))
      (node (ref "R29") (pin "2") (pinfunction "2_2") (pintype "passive"))
      (node (ref "U$11") (pin "2") (pinfunction "OUT2_2") (pintype "bidirectional"))
    )
    (net (code "89") (name "Net-(U$12-N_FAULT)") (class "Default")
      (node (ref "R42") (pin "2") (pinfunction "2_2") (pintype "passive"))
      (node (ref "U$12") (pin "6") (pinfunction "N_FAULT_6") (pintype "bidirectional"))
    )
    (net (code "90") (name "Net-(U$14-1)") (class "Default")
      (node (ref "JP1") (pin "1") (pinfunction "1_1") (pintype "passive"))
      (node (ref "U$14") (pin "P$1") (pinfunction "1_P$1") (pintype "bidirectional"))
    )
    (net (code "91") (name "Net-(U$17-N_FAULT)") (class "Default")
      (node (ref "R41") (pin "1") (pinfunction "1_1") (pintype "passive"))
      (node (ref "U$17") (pin "6") (pinfunction "N_FAULT_6") (pintype "bidirectional"))
    )
    (net (code "92") (name "Net-(U4-PB0)") (class "Default")
      (node (ref "JP9") (pin "4") (pinfunction "4_4") (pintype "passive"))
      (node (ref "U4") (pin "4") (pinfunction "PB0_4") (pintype "bidirectional"))
    )
    (net (code "93") (name "Net-(U4-PB1)") (class "Default")
      (node (ref "JP9") (pin "3") (pinfunction "3_3") (pintype "passive"))
      (node (ref "U4") (pin "5") (pinfunction "PB1_5") (pintype "bidirectional"))
    )
    (net (code "94") (name "Net-(U4-PR0)") (class "Default")
      (node (ref "C9") (pin "1") (pinfunction "1_1") (pintype "passive"))
      (node (ref "Q1") (pin "1") (pinfunction "1_1") (pintype "passive"))
      (node (ref "U4") (pin "36") (pinfunction "PR0_36") (pintype "bidirectional"))
    )
    (net (code "95") (name "Net-(U4-PR1)") (class "Default")
      (node (ref "C8") (pin "1") (pinfunction "1_1") (pintype "passive"))
      (node (ref "Q1") (pin "2") (pinfunction "2_2") (pintype "passive"))
      (node (ref "U4") (pin "37") (pinfunction "PR1_37") (pintype "bidirectional"))
    )
    (net (code "96") (name "unconnected-(JP2-Pad1)") (class "Default")
      (node (ref "JP2") (pin "1") (pinfunction "1_1") (pintype "passive"))
    )
    (net (code "97") (name "unconnected-(JP2-Pad2)") (class "Default")
      (node (ref "JP2") (pin "2") (pinfunction "2_2") (pintype "passive"))
    )
    (net (code "98") (name "unconnected-(JP3-Pad1)") (class "Default")
      (node (ref "JP3") (pin "1") (pinfunction "1_1") (pintype "passive"))
    )
    (net (code "99") (name "unconnected-(JP3-Pad2)") (class "Default")
      (node (ref "JP3") (pin "2") (pinfunction "2_2") (pintype "passive"))
    )
    (net (code "100") (name "unconnected-(S1-P$1-PadP1)") (class "Default")
      (node (ref "S1") (pin "P1") (pinfunction "P$1_P1") (pintype "bidirectional"))
    )
    (net (code "101") (name "unconnected-(S2-P$1-PadP1)") (class "Default")
      (node (ref "S2") (pin "P1") (pinfunction "P$1_P1") (pintype "bidirectional"))
    )
    (net (code "102") (name "unconnected-(S3-P$1-PadP1)") (class "Default")
      (node (ref "S3") (pin "P1") (pinfunction "P$1_P1") (pintype "bidirectional"))
    )
    (net (code "103") (name "unconnected-(S4-P$1-PadP1)") (class "Default")
      (node (ref "S4") (pin "P1") (pinfunction "P$1_P1") (pintype "bidirectional"))
    )
    (net (code "104") (name "unconnected-(SV2-Pad3)") (class "Default")
      (node (ref "SV2") (pin "3") (pinfunction "3_3") (pintype "passive"))
    )
    (net (code "105") (name "unconnected-(SV2-Pad4)") (class "Default")
      (node (ref "SV2") (pin "4") (pinfunction "4_4") (pintype "passive"))
    )
    (net (code "106") (name "unconnected-(SV9-Pad5)") (class "Default")
      (node (ref "SV9") (pin "5") (pinfunction "5_5") (pintype "passive"))
    )
    (net (code "107") (name "unconnected-(SV9-Pad7)") (class "Default")
      (node (ref "SV9") (pin "7") (pinfunction "7_7") (pintype "passive"))
    )
    (net (code "108") (name "unconnected-(U4-PA0-Pad40)") (class "Default")
      (node (ref "U4") (pin "40") (pinfunction "PA0_40") (pintype "bidirectional"))
    )
    (net (code "109") (name "unconnected-(U4-PB3-Pad7)") (class "Default")
      (node (ref "U4") (pin "7") (pinfunction "PB3_7") (pintype "bidirectional"))
    )
    (net (code "110") (name "unconnected-(U4-PD0-Pad20)") (class "Default")
      (node (ref "U4") (pin "20") (pinfunction "PD0_20") (pintype "bidirectional"))
    )
    (net (code "111") (name "unconnected-(U4-PD1-Pad21)") (class "Default")
      (node (ref "U4") (pin "21") (pinfunction "PD1_21") (pintype "bidirectional"))
    )
    (net (code "112") (name "unconnected-(U4-PD6-Pad26)") (class "Default")
      (node (ref "U4") (pin "26") (pinfunction "PD6_26") (pintype "bidirectional"))
    )
  )
)
